# SCH_TRANSMITTER-WITH-ATMEGA328-VER-1_2_2.net
KiCad netlist of a schematic drawn in EasyEDA
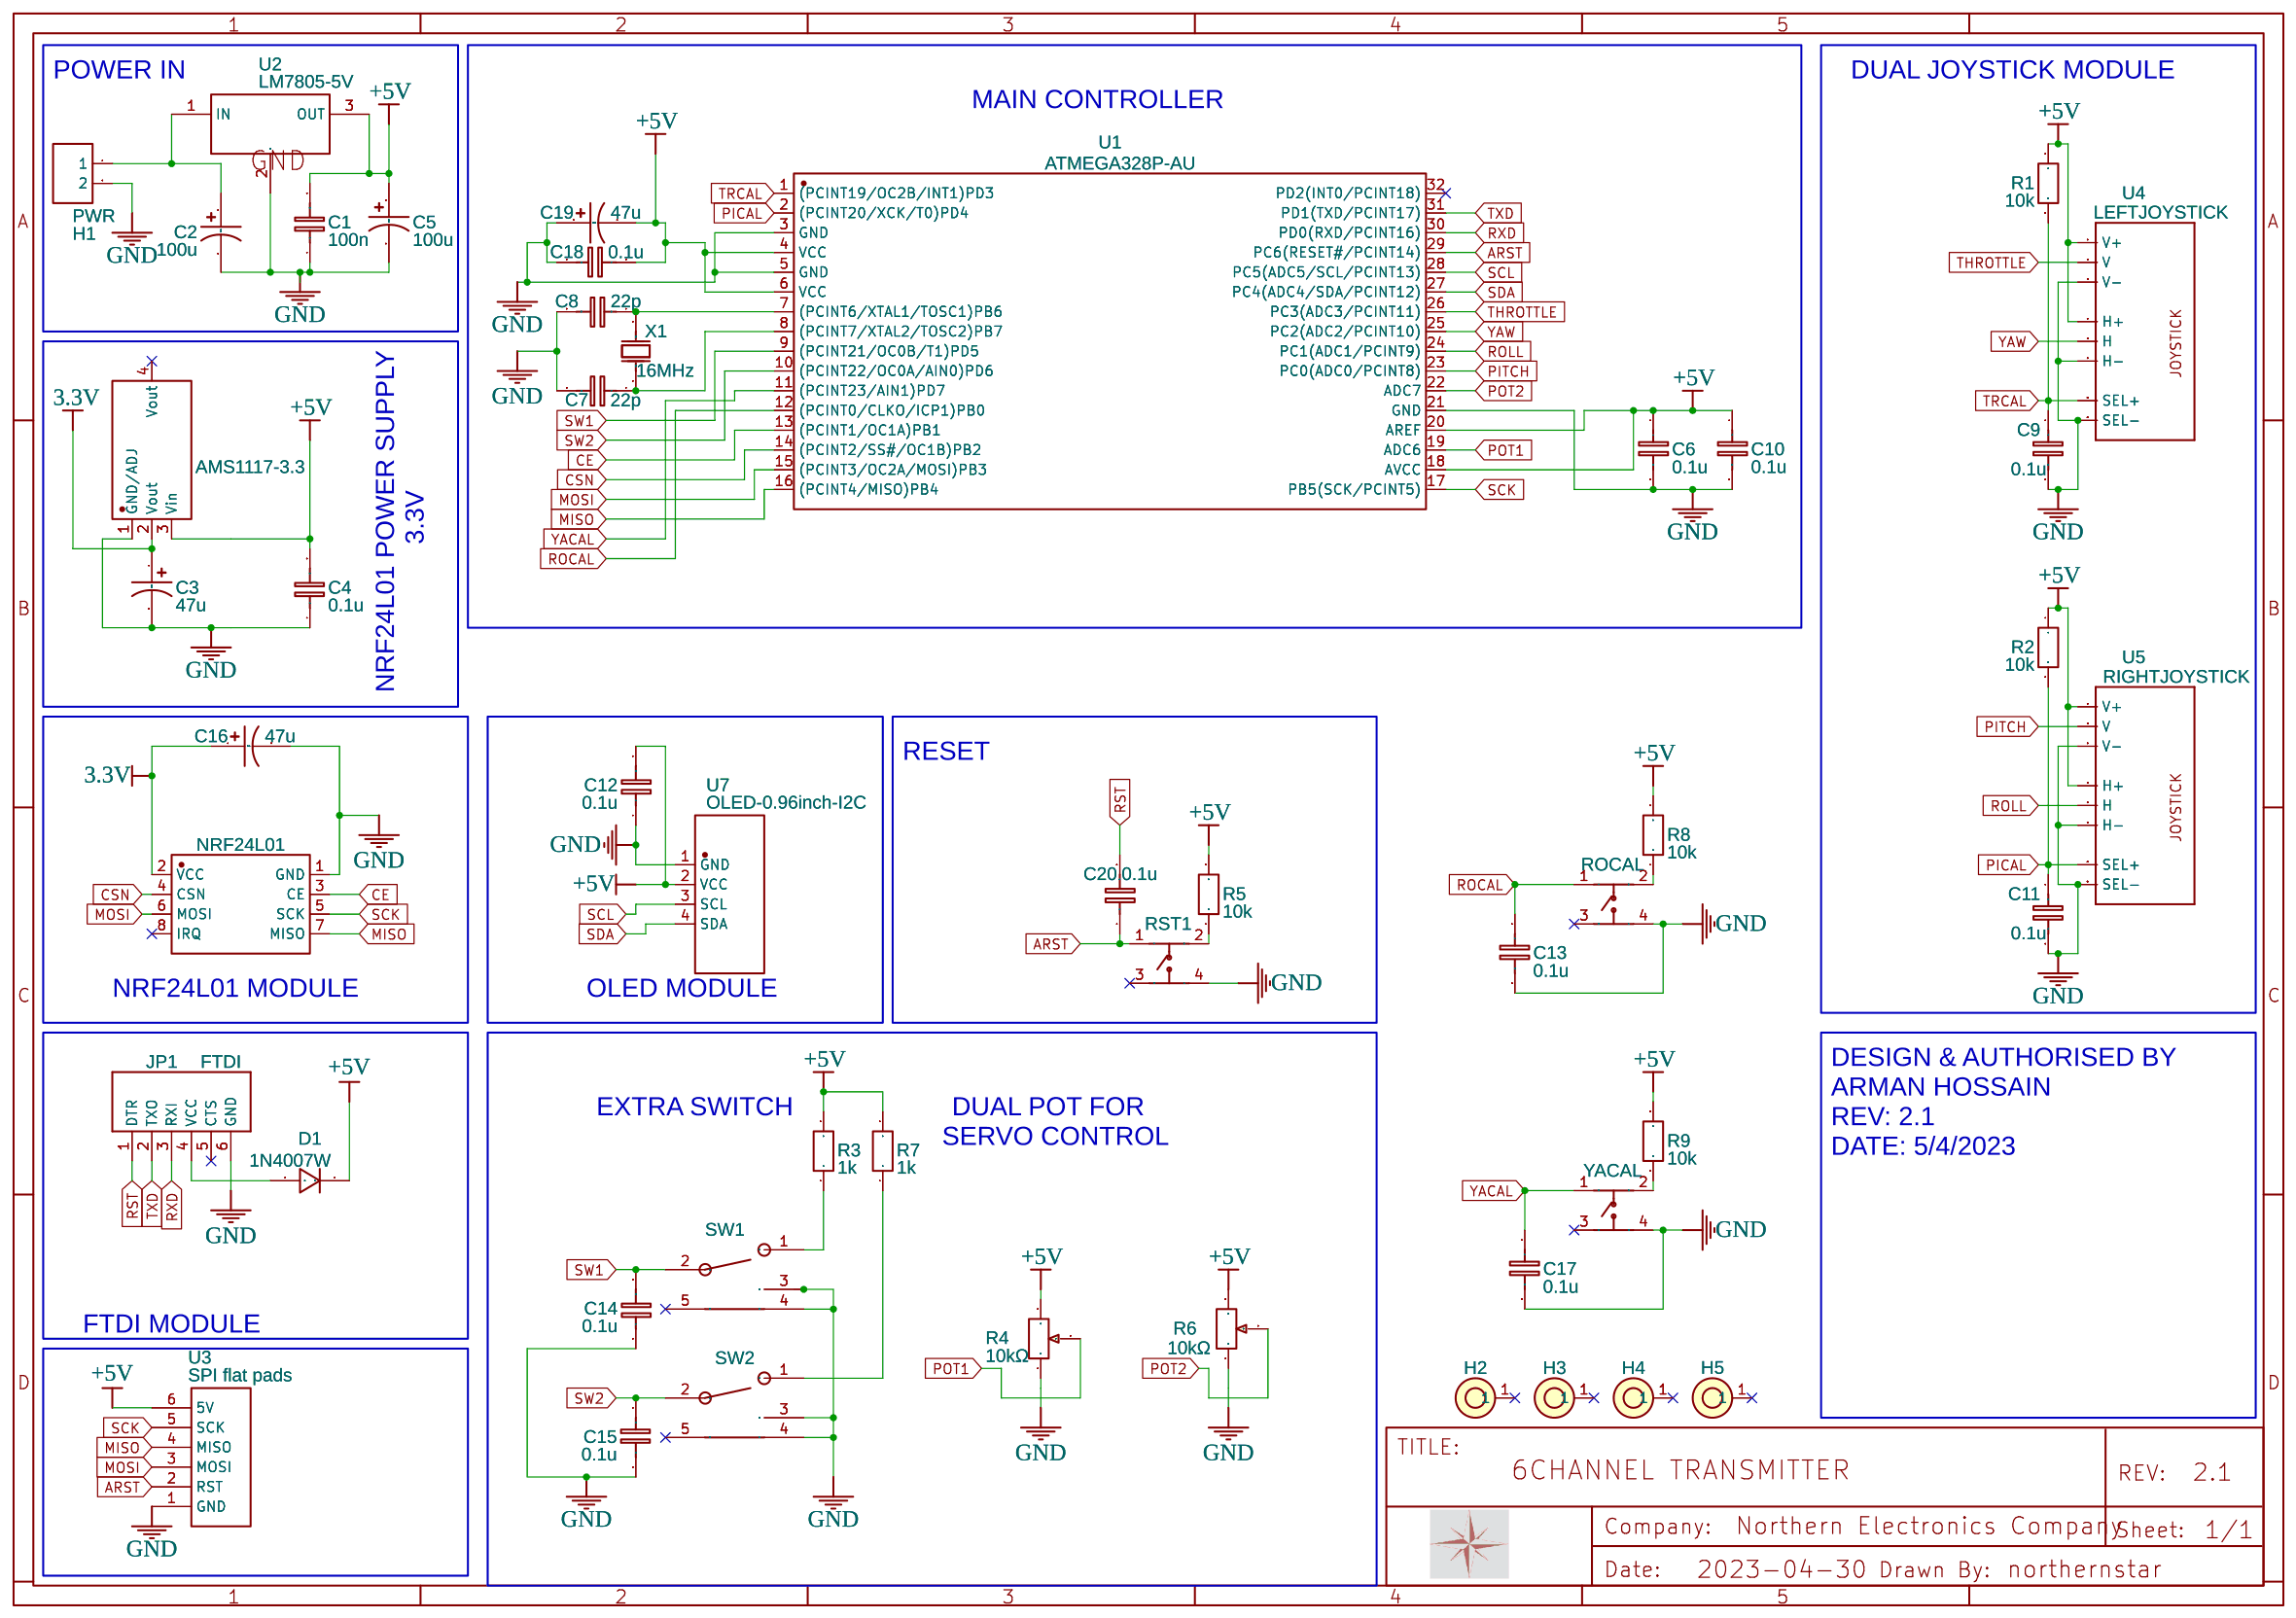
[diagram p0: schematic sheet]

(export (version "E")
  (design (tool "Eeschema 10.0.6"))
  (components
    (comp (ref "C1") (value "100n") (libsource (lib "") (part "C_RAD-0.2_EU_1")))
    (comp (ref "C2") (value "100u") (libsource (lib "") (part "CE_TH_D5.0×F2.0_US_2")))
    (comp (ref "C3") (value "47u") (libsource (lib "") (part "CE_TH_D5.0×F2.0_US_1")))
    (comp (ref "C4") (value "0.1u") (libsource (lib "") (part "C_1206_EU_3")))
    (comp (ref "C5") (value "100u") (libsource (lib "") (part "CE_TH_D5.0×F2.0_US_2")))
    (comp (ref "C6") (value "0.1u") (libsource (lib "") (part "C_1206_EU_5")))
    (comp (ref "C7") (value "22p") (libsource (lib "") (part "C_RAD-0.2_EU")))
    (comp (ref "C8") (value "22p") (libsource (lib "") (part "C_RAD-0.2_EU")))
    (comp (ref "C9") (value "0.1u") (libsource (lib "") (part "C_1206_EU_4")))
    (comp (ref "C10") (value "0.1u") (libsource (lib "") (part "C_1206_EU_5")))
    (comp (ref "C11") (value "0.1u") (libsource (lib "") (part "C_1206_EU_1")))
    (comp (ref "C12") (value "0.1u") (libsource (lib "") (part "C_1206_EU_6")))
    (comp (ref "C13") (value "0.1u") (libsource (lib "") (part "C_1206_EU_1")))
    (comp (ref "C14") (value "0.1u") (libsource (lib "") (part "C_1206_EU_6")))
    (comp (ref "C15") (value "0.1u") (libsource (lib "") (part "C_1206_EU_7")))
    (comp (ref "C16") (value "47u") (libsource (lib "") (part "CE_TH_D5.0×F2.0_US")))
    (comp (ref "C17") (value "0.1u") (libsource (lib "") (part "C_1206_EU_1")))
    (comp (ref "C18") (value "0.1u") (libsource (lib "") (part "C_1206_EU_2")))
    (comp (ref "C19") (value "47u") (libsource (lib "") (part "CE_TH_D5.0×F2.0_US_3")))
    (comp (ref "C20") (value "0.1u") (libsource (lib "") (part "C_1206_EU")))
    (comp (ref "D1")
      (value "1N4007W")
      (fields (field (name "Manufacturer") "BLUE ROCKET"))
      (libsource (lib "") (part "1N4007W"))
    )
    (comp (ref "H1") (value "PWR") (libsource (lib "") (part "HDR-F-2.54_1x2")))
    (comp (ref "H2") (value "M3 HOLE PLATED") (libsource (lib "") (part "M3 HOLE PLATED")))
    (comp (ref "H3") (value "M3 HOLE PLATED") (libsource (lib "") (part "M3 HOLE PLATED")))
    (comp (ref "H4") (value "M3 HOLE PLATED") (libsource (lib "") (part "M3 HOLE PLATED")))
    (comp (ref "H5") (value "M3 HOLE PLATED") (libsource (lib "") (part "M3 HOLE PLATED")))
    (comp (ref "JP1") (value "FTDI") (libsource (lib "") (part "FTDI")))
    (comp (ref "MK1")
      (value "NRF24L01")
      (fields (field (name "Manufacturer Part") "NF-04") (field (name "Manufacturer") "Ai-Thinker(安信可)"))
      (libsource (lib "") (part "NRF24L01"))
    )
    (comp (ref "NO1")
      (value "AMS1117-3.3")
      (fields (field (name "Manufacturer Part") "AMS1117-3.3-YJLTY"))
      (libsource (lib "") (part "AMS1117-3.3-YJLTY"))
    )
    (comp (ref "R1") (value "10k") (libsource (lib "") (part "R_1206_EU")))
    (comp (ref "R2") (value "10k") (libsource (lib "") (part "R_1206_EU")))
    (comp (ref "R3") (value "1k") (libsource (lib "") (part "R_1206_EU_1")))
    (comp (ref "R4")
      (value "10kΩ")
      (fields
        (field (name "Manufacturer Part") "RK16312A0BKH")
        (field (name "Manufacturer") "ALPSALPINE(阿尔卑斯阿尔派)")
      )
      (libsource (lib "") (part "A10K"))
    )
    (comp (ref "R5") (value "10k") (libsource (lib "") (part "R_1206_EU_1")))
    (comp (ref "R6")
      (value "10kΩ")
      (fields
        (field (name "Manufacturer Part") "RK16312A0BKH")
        (field (name "Manufacturer") "ALPSALPINE(阿尔卑斯阿尔派)")
      )
      (libsource (lib "") (part "A10K"))
    )
    (comp (ref "R7") (value "1k") (libsource (lib "") (part "R_1206_EU_1")))
    (comp (ref "R8") (value "10k") (libsource (lib "") (part "R_1206_EU_1")))
    (comp (ref "R9") (value "10k") (libsource (lib "") (part "R_1206_EU_1")))
    (comp (ref "ROCAL")
      (value "TSD001A08526A")
      (fields (field (name "Manufacturer") "BZCN(博众电气)"))
      (libsource (lib "") (part "TSD001A08526A_2"))
    )
    (comp (ref "RST1")
      (value "TSD001A08526A")
      (fields (field (name "Manufacturer") "BZCN(博众电气)"))
      (libsource (lib "") (part "TSD001A08526A"))
    )
    (comp (ref "SW1")
      (value "SW")
      (fields (field (name "Manufacturer Part") "100SP3T2B4M6RE") (field (name "Manufacturer") "E-Switch"))
      (libsource (lib "") (part "100SP3T2B4M6RE"))
    )
    (comp (ref "SW2")
      (value "100SP3T2B4M6RE")
      (fields (field (name "Manufacturer") "E-Switch"))
      (libsource (lib "") (part "100SP3T2B4M6RE"))
    )
    (comp (ref "U1") (value "ATMEGA328P-AU") (libsource (lib "") (part "ATMEGA328P-AU_C2851158")))
    (comp (ref "U2") (value "LM7805-5V") (libsource (lib "") (part "LM7805-5V")))
    (comp (ref "U3") (value "SPI flat pads") (libsource (lib "") (part "SPI flat pads")))
    (comp (ref "U4") (value "LEFTJOYSTICK") (libsource (lib "") (part "JOYSTICKPTH")))
    (comp (ref "U5") (value "RIGHTJOYSTICK") (libsource (lib "") (part "JOYSTICKPTH")))
    (comp (ref "U7")
      (value "OLED-0.96inch-I2C")
      (fields
        (field (name "Manufacturer Part") "ZJY096S0700BG01蓝色")
        (field (name "Manufacturer") "AZDelivery")
      )
      (libsource (lib "") (part "OLED-0.96inch-I2C"))
    )
    (comp (ref "X1")
      (value "16MHz")
      (fields (field (name "Manufacturer Part") "X49SD16MSD2SC") (field (name "Manufacturer") "YXC(扬兴晶振)"))
      (libsource (lib "") (part "X49SD16MSD2SC"))
    )
    (comp (ref "YACAL")
      (value "TSD001A08526A")
      (fields (field (name "Manufacturer") "BZCN(博众电气)"))
      (libsource (lib "") (part "TSD001A08526A_1"))
    )
  )
  (nets
    (net (code "1") (name "+5V") (class "Default")
      (node (ref "C1") (pin "2") (pinfunction "2_2") (pintype "unspecified"))
      (node (ref "C10") (pin "1") (pinfunction "1_1") (pintype "unspecified"))
      (node (ref "C12") (pin "2") (pinfunction "2_2") (pintype "unspecified"))
      (node (ref "C18") (pin "2") (pinfunction "2_2") (pintype "unspecified"))
      (node (ref "C19") (pin "2") (pinfunction "2_2") (pintype "unspecified"))
      (node (ref "C4") (pin "2") (pinfunction "2_2") (pintype "unspecified"))
      (node (ref "C5") (pin "1") (pinfunction "1_1") (pintype "unspecified"))
      (node (ref "C6") (pin "1") (pinfunction "1_1") (pintype "unspecified"))
      (node (ref "D1") (pin "1") (pinfunction "1_1") (pintype "unspecified"))
      (node (ref "NO1") (pin "3") (pinfunction "Vin_3") (pintype "unspecified"))
      (node (ref "R1") (pin "1") (pinfunction "1_1") (pintype "unspecified"))
      (node (ref "R2") (pin "1") (pinfunction "1_1") (pintype "unspecified"))
      (node (ref "R3") (pin "2") (pinfunction "2_2") (pintype "unspecified"))
      (node (ref "R4") (pin "3") (pinfunction "3_3") (pintype "input"))
      (node (ref "R5") (pin "2") (pinfunction "2_2") (pintype "unspecified"))
      (node (ref "R6") (pin "3") (pinfunction "3_3") (pintype "input"))
      (node (ref "R7") (pin "2") (pinfunction "2_2") (pintype "unspecified"))
      (node (ref "R8") (pin "2") (pinfunction "2_2") (pintype "unspecified"))
      (node (ref "R9") (pin "2") (pinfunction "2_2") (pintype "unspecified"))
      (node (ref "U1") (pin "18") (pinfunction "AVCC_18") (pintype "unspecified"))
      (node (ref "U1") (pin "20") (pinfunction "AREF_20") (pintype "unspecified"))
      (node (ref "U1") (pin "4") (pinfunction "VCC_4") (pintype "unspecified"))
      (node (ref "U1") (pin "6") (pinfunction "VCC_6") (pintype "unspecified"))
      (node (ref "U2") (pin "3") (pinfunction "OUT_3") (pintype "passive"))
      (node (ref "U3") (pin "6") (pinfunction "5V_6") (pintype "unspecified"))
      (node (ref "U4") (pin "H1") (pinfunction "H+_H1") (pintype "bidirectional"))
      (node (ref "U4") (pin "V1") (pinfunction "V+_V1") (pintype "bidirectional"))
      (node (ref "U5") (pin "H1") (pinfunction "H+_H1") (pintype "bidirectional"))
      (node (ref "U5") (pin "V1") (pinfunction "V+_V1") (pintype "bidirectional"))
      (node (ref "U7") (pin "2") (pinfunction "VCC_2") (pintype "unspecified"))
    )
    (net (code "2") (name "3.3V") (class "Default")
      (node (ref "C16") (pin "1") (pinfunction "1_1") (pintype "unspecified"))
      (node (ref "C3") (pin "1") (pinfunction "1_1") (pintype "unspecified"))
      (node (ref "MK1") (pin "2") (pinfunction "VCC_2") (pintype "unspecified"))
      (node (ref "NO1") (pin "2") (pinfunction "Vout_2") (pintype "unspecified"))
    )
    (net (code "3") (name "ARST") (class "Default")
      (node (ref "C20") (pin "1") (pinfunction "1_1") (pintype "unspecified"))
      (node (ref "RST1") (pin "1") (pinfunction "1_1") (pintype "unspecified"))
      (node (ref "U1") (pin "29") (pinfunction "PC6(RESET#/PCINT14)_29") (pintype "unspecified"))
      (node (ref "U3") (pin "2") (pinfunction "RST_2") (pintype "unspecified"))
    )
    (net (code "4") (name "CE") (class "Default")
      (node (ref "MK1") (pin "3") (pinfunction "CE_3") (pintype "unspecified"))
      (node (ref "U1") (pin "13") (pinfunction "(PCINT1/OC1A)PB1_13") (pintype "unspecified"))
    )
    (net (code "5") (name "CSN") (class "Default")
      (node (ref "MK1") (pin "4") (pinfunction "CSN_4") (pintype "unspecified"))
      (node (ref "U1") (pin "14") (pinfunction "(PCINT2/SS#/OC1B)PB2_14") (pintype "unspecified"))
    )
    (net (code "6") (name "GND") (class "Default")
      (node (ref "C1") (pin "1") (pinfunction "1_1") (pintype "unspecified"))
      (node (ref "C10") (pin "2") (pinfunction "2_2") (pintype "unspecified"))
      (node (ref "C11") (pin "2") (pinfunction "2_2") (pintype "unspecified"))
      (node (ref "C12") (pin "1") (pinfunction "1_1") (pintype "unspecified"))
      (node (ref "C13") (pin "2") (pinfunction "2_2") (pintype "unspecified"))
      (node (ref "C14") (pin "1") (pinfunction "1_1") (pintype "unspecified"))
      (node (ref "C15") (pin "2") (pinfunction "2_2") (pintype "unspecified"))
      (node (ref "C16") (pin "2") (pinfunction "2_2") (pintype "unspecified"))
      (node (ref "C17") (pin "2") (pinfunction "2_2") (pintype "unspecified"))
      (node (ref "C18") (pin "1") (pinfunction "1_1") (pintype "unspecified"))
      (node (ref "C19") (pin "1") (pinfunction "1_1") (pintype "unspecified"))
      (node (ref "C2") (pin "2") (pinfunction "2_2") (pintype "unspecified"))
      (node (ref "C3") (pin "2") (pinfunction "2_2") (pintype "unspecified"))
      (node (ref "C4") (pin "1") (pinfunction "1_1") (pintype "unspecified"))
      (node (ref "C5") (pin "2") (pinfunction "2_2") (pintype "unspecified"))
      (node (ref "C6") (pin "2") (pinfunction "2_2") (pintype "unspecified"))
      (node (ref "C7") (pin "2") (pinfunction "2_2") (pintype "unspecified"))
      (node (ref "C8") (pin "2") (pinfunction "2_2") (pintype "unspecified"))
      (node (ref "C9") (pin "2") (pinfunction "2_2") (pintype "unspecified"))
      (node (ref "H1") (pin "2") (pinfunction "2_2") (pintype "input"))
      (node (ref "JP1") (pin "6") (pinfunction "GND_6") (pintype "unspecified"))
      (node (ref "MK1") (pin "1") (pinfunction "GND_1") (pintype "unspecified"))
      (node (ref "NO1") (pin "1") (pinfunction "GND/ADJ_1") (pintype "unspecified"))
      (node (ref "R4") (pin "1") (pinfunction "1_1") (pintype "input"))
      (node (ref "R6") (pin "1") (pinfunction "1_1") (pintype "input"))
      (node (ref "ROCAL") (pin "4") (pinfunction "4_4") (pintype "unspecified"))
      (node (ref "RST1") (pin "4") (pinfunction "4_4") (pintype "unspecified"))
      (node (ref "SW1") (pin "3") (pinfunction "3_3") (pintype "input"))
      (node (ref "SW1") (pin "4") (pinfunction "4_4") (pintype "unspecified"))
      (node (ref "SW2") (pin "3") (pinfunction "3_3") (pintype "input"))
      (node (ref "SW2") (pin "4") (pinfunction "4_4") (pintype "unspecified"))
      (node (ref "U1") (pin "21") (pinfunction "GND_21") (pintype "unspecified"))
      (node (ref "U1") (pin "3") (pinfunction "GND_3") (pintype "unspecified"))
      (node (ref "U1") (pin "5") (pinfunction "GND_5") (pintype "unspecified"))
      (node (ref "U2") (pin "2") (pinfunction "GND_2") (pintype "passive"))
      (node (ref "U3") (pin "1") (pinfunction "GND_1") (pintype "unspecified"))
      (node (ref "U4") (pin "B2A") (pinfunction "SEL-_B2A") (pintype "bidirectional"))
      (node (ref "U4") (pin "H3") (pinfunction "H-_H3") (pintype "bidirectional"))
      (node (ref "U4") (pin "V3") (pinfunction "V-_V3") (pintype "bidirectional"))
      (node (ref "U5") (pin "B2A") (pinfunction "SEL-_B2A") (pintype "bidirectional"))
      (node (ref "U5") (pin "H3") (pinfunction "H-_H3") (pintype "bidirectional"))
      (node (ref "U5") (pin "V3") (pinfunction "V-_V3") (pintype "bidirectional"))
      (node (ref "U7") (pin "1") (pinfunction "GND_1") (pintype "unspecified"))
      (node (ref "YACAL") (pin "4") (pinfunction "4_4") (pintype "unspecified"))
    )
    (net (code "7") (name "MISO") (class "Default")
      (node (ref "MK1") (pin "7") (pinfunction "MISO_7") (pintype "unspecified"))
      (node (ref "U1") (pin "16") (pinfunction "(PCINT4/MISO)PB4_16") (pintype "unspecified"))
      (node (ref "U3") (pin "4") (pinfunction "MISO_4") (pintype "unspecified"))
    )
    (net (code "8") (name "MOSI") (class "Default")
      (node (ref "MK1") (pin "6") (pinfunction "MOSI_6") (pintype "unspecified"))
      (node (ref "U1") (pin "15") (pinfunction "(PCINT3/OC2A/MOSI)PB3_15") (pintype "unspecified"))
      (node (ref "U3") (pin "3") (pinfunction "MOSI_3") (pintype "unspecified"))
    )
    (net (code "9") (name "Net-(JP1-VCC)") (class "Default")
      (node (ref "D1") (pin "2") (pinfunction "2_2") (pintype "unspecified"))
      (node (ref "JP1") (pin "4") (pinfunction "VCC_4") (pintype "unspecified"))
    )
    (net (code "10") (name "Net-(R3-Pad1)") (class "Default")
      (node (ref "R3") (pin "1") (pinfunction "1_1") (pintype "unspecified"))
      (node (ref "SW1") (pin "1") (pinfunction "1_1") (pintype "input"))
    )
    (net (code "11") (name "Net-(R5-Pad1)") (class "Default")
      (node (ref "R5") (pin "1") (pinfunction "1_1") (pintype "unspecified"))
      (node (ref "RST1") (pin "2") (pinfunction "2_2") (pintype "unspecified"))
    )
    (net (code "12") (name "Net-(R7-Pad1)") (class "Default")
      (node (ref "R7") (pin "1") (pinfunction "1_1") (pintype "unspecified"))
      (node (ref "SW2") (pin "1") (pinfunction "1_1") (pintype "input"))
    )
    (net (code "13") (name "Net-(R8-Pad1)") (class "Default")
      (node (ref "R8") (pin "1") (pinfunction "1_1") (pintype "unspecified"))
      (node (ref "ROCAL") (pin "2") (pinfunction "2_2") (pintype "unspecified"))
    )
    (net (code "14") (name "Net-(R9-Pad1)") (class "Default")
      (node (ref "R9") (pin "1") (pinfunction "1_1") (pintype "unspecified"))
      (node (ref "YACAL") (pin "2") (pinfunction "2_2") (pintype "unspecified"))
    )
    (net (code "15") (name "Net-(U1-(PCINT6{slash}XTAL1{slash}TOSC1)PB6)") (class "Default")
      (node (ref "C8") (pin "1") (pinfunction "1_1") (pintype "unspecified"))
      (node (ref "U1") (pin "7") (pinfunction "(PCINT6/XTAL1/TOSC1)PB6_7") (pintype "unspecified"))
      (node (ref "X1") (pin "1") (pinfunction "OSC1_1") (pintype "input"))
    )
    (net (code "16") (name "Net-(U1-(PCINT7{slash}XTAL2{slash}TOSC2)PB7)") (class "Default")
      (node (ref "C7") (pin "1") (pinfunction "1_1") (pintype "unspecified"))
      (node (ref "U1") (pin "8") (pinfunction "(PCINT7/XTAL2/TOSC2)PB7_8") (pintype "unspecified"))
      (node (ref "X1") (pin "2") (pinfunction "OSC2_2") (pintype "input"))
    )
    (net (code "17") (name "Net-(U2-IN)") (class "Default")
      (node (ref "C2") (pin "1") (pinfunction "1_1") (pintype "unspecified"))
      (node (ref "H1") (pin "1") (pinfunction "1_1") (pintype "input"))
      (node (ref "U2") (pin "1") (pinfunction "IN_1") (pintype "passive"))
    )
    (net (code "18") (name "PICAL") (class "Default")
      (node (ref "C11") (pin "1") (pinfunction "1_1") (pintype "unspecified"))
      (node (ref "R2") (pin "2") (pinfunction "2_2") (pintype "unspecified"))
      (node (ref "U1") (pin "2") (pinfunction "(PCINT20/XCK/T0)PD4_2") (pintype "unspecified"))
      (node (ref "U5") (pin "B1A") (pinfunction "SEL+_B1A") (pintype "bidirectional"))
    )
    (net (code "19") (name "PITCH") (class "Default")
      (node (ref "U1") (pin "23") (pinfunction "PC0(ADC0/PCINT8)_23") (pintype "unspecified"))
      (node (ref "U5") (pin "V2") (pinfunction "V_V2") (pintype "bidirectional"))
    )
    (net (code "20") (name "POT1") (class "Default")
      (node (ref "R4") (pin "2") (pinfunction "2_2") (pintype "input"))
      (node (ref "U1") (pin "19") (pinfunction "ADC6_19") (pintype "unspecified"))
    )
    (net (code "21") (name "POT2") (class "Default")
      (node (ref "R6") (pin "2") (pinfunction "2_2") (pintype "input"))
      (node (ref "U1") (pin "22") (pinfunction "ADC7_22") (pintype "unspecified"))
    )
    (net (code "22") (name "ROCAL") (class "Default")
      (node (ref "C13") (pin "1") (pinfunction "1_1") (pintype "unspecified"))
      (node (ref "ROCAL") (pin "1") (pinfunction "1_1") (pintype "unspecified"))
      (node (ref "U1") (pin "12") (pinfunction "(PCINT0/CLKO/ICP1)PB0_12") (pintype "unspecified"))
    )
    (net (code "23") (name "ROLL") (class "Default")
      (node (ref "U1") (pin "24") (pinfunction "PC1(ADC1/PCINT9)_24") (pintype "unspecified"))
      (node (ref "U5") (pin "H2") (pinfunction "H_H2") (pintype "bidirectional"))
    )
    (net (code "24") (name "RST") (class "Default")
      (node (ref "C20") (pin "2") (pinfunction "2_2") (pintype "unspecified"))
      (node (ref "JP1") (pin "1") (pinfunction "DTR_1") (pintype "unspecified"))
    )
    (net (code "25") (name "RXD") (class "Default")
      (node (ref "JP1") (pin "3") (pinfunction "RXI_3") (pintype "unspecified"))
      (node (ref "U1") (pin "30") (pinfunction "PD0(RXD/PCINT16)_30") (pintype "unspecified"))
    )
    (net (code "26") (name "SCK") (class "Default")
      (node (ref "MK1") (pin "5") (pinfunction "SCK_5") (pintype "unspecified"))
      (node (ref "U1") (pin "17") (pinfunction "PB5(SCK/PCINT5)_17") (pintype "unspecified"))
      (node (ref "U3") (pin "5") (pinfunction "SCK_5") (pintype "unspecified"))
    )
    (net (code "27") (name "SCL") (class "Default")
      (node (ref "U1") (pin "28") (pinfunction "PC5(ADC5/SCL/PCINT13)_28") (pintype "unspecified"))
      (node (ref "U7") (pin "3") (pinfunction "SCL_3") (pintype "unspecified"))
    )
    (net (code "28") (name "SDA") (class "Default")
      (node (ref "U1") (pin "27") (pinfunction "PC4(ADC4/SDA/PCINT12)_27") (pintype "unspecified"))
      (node (ref "U7") (pin "4") (pinfunction "SDA_4") (pintype "unspecified"))
    )
    (net (code "29") (name "SW1") (class "Default")
      (node (ref "C14") (pin "2") (pinfunction "2_2") (pintype "unspecified"))
      (node (ref "SW1") (pin "2") (pinfunction "2_2") (pintype "input"))
      (node (ref "U1") (pin "9") (pinfunction "(PCINT21/OC0B/T1)PD5_9") (pintype "unspecified"))
    )
    (net (code "30") (name "SW2") (class "Default")
      (node (ref "C15") (pin "1") (pinfunction "1_1") (pintype "unspecified"))
      (node (ref "SW2") (pin "2") (pinfunction "2_2") (pintype "input"))
      (node (ref "U1") (pin "10") (pinfunction "(PCINT22/OC0A/AIN0)PD6_10") (pintype "unspecified"))
    )
    (net (code "31") (name "THROTTLE") (class "Default")
      (node (ref "U1") (pin "26") (pinfunction "PC3(ADC3/PCINT11)_26") (pintype "unspecified"))
      (node (ref "U4") (pin "V2") (pinfunction "V_V2") (pintype "bidirectional"))
    )
    (net (code "32") (name "TRCAL") (class "Default")
      (node (ref "C9") (pin "1") (pinfunction "1_1") (pintype "unspecified"))
      (node (ref "R1") (pin "2") (pinfunction "2_2") (pintype "unspecified"))
      (node (ref "U1") (pin "1") (pinfunction "(PCINT19/OC2B/INT1)PD3_1") (pintype "unspecified"))
      (node (ref "U4") (pin "B1A") (pinfunction "SEL+_B1A") (pintype "bidirectional"))
    )
    (net (code "33") (name "TXD") (class "Default")
      (node (ref "JP1") (pin "2") (pinfunction "TXO_2") (pintype "unspecified"))
      (node (ref "U1") (pin "31") (pinfunction "PD1(TXD/PCINT17)_31") (pintype "unspecified"))
    )
    (net (code "34") (name "YACAL") (class "Default")
      (node (ref "C17") (pin "1") (pinfunction "1_1") (pintype "unspecified"))
      (node (ref "U1") (pin "11") (pinfunction "(PCINT23/AIN1)PD7_11") (pintype "unspecified"))
      (node (ref "YACAL") (pin "1") (pinfunction "1_1") (pintype "unspecified"))
    )
    (net (code "35") (name "YAW") (class "Default")
      (node (ref "U1") (pin "25") (pinfunction "PC2(ADC2/PCINT10)_25") (pintype "unspecified"))
      (node (ref "U4") (pin "H2") (pinfunction "H_H2") (pintype "bidirectional"))
    )
    (net (code "36") (name "unconnected-(H2-Pad1)") (class "Default")
      (node (ref "H2") (pin "1") (pinfunction "1_1") (pintype "unspecified+no_connect"))
    )
    (net (code "37") (name "unconnected-(H3-Pad1)") (class "Default")
      (node (ref "H3") (pin "1") (pinfunction "1_1") (pintype "unspecified+no_connect"))
    )
    (net (code "38") (name "unconnected-(H4-Pad1)") (class "Default")
      (node (ref "H4") (pin "1") (pinfunction "1_1") (pintype "unspecified+no_connect"))
    )
    (net (code "39") (name "unconnected-(H5-Pad1)") (class "Default")
      (node (ref "H5") (pin "1") (pinfunction "1_1") (pintype "unspecified+no_connect"))
    )
    (net (code "40") (name "unconnected-(JP1-CTS-Pad5)") (class "Default")
      (node (ref "JP1") (pin "5") (pinfunction "CTS_5") (pintype "unspecified+no_connect"))
    )
    (net (code "41") (name "unconnected-(MK1-IRQ-Pad8)") (class "Default")
      (node (ref "MK1") (pin "8") (pinfunction "IRQ_8") (pintype "unspecified+no_connect"))
    )
    (net (code "42") (name "unconnected-(NO1-Vout-Pad4)") (class "Default")
      (node (ref "NO1") (pin "4") (pinfunction "Vout_4") (pintype "unspecified+no_connect"))
    )
    (net (code "43") (name "unconnected-(ROCAL-Pad3)") (class "Default")
      (node (ref "ROCAL") (pin "3") (pinfunction "3_3") (pintype "unspecified+no_connect"))
    )
    (net (code "44") (name "unconnected-(RST1-Pad3)") (class "Default")
      (node (ref "RST1") (pin "3") (pinfunction "3_3") (pintype "unspecified+no_connect"))
    )
    (net (code "45") (name "unconnected-(SW1-Pad5)") (class "Default")
      (node (ref "SW1") (pin "5") (pinfunction "5_5") (pintype "unspecified+no_connect"))
    )
    (net (code "46") (name "unconnected-(SW2-Pad5)") (class "Default")
      (node (ref "SW2") (pin "5") (pinfunction "5_5") (pintype "unspecified+no_connect"))
    )
    (net (code "47") (name "unconnected-(U1-PD2(INT0{slash}PCINT18)-Pad32)") (class "Default")
      (node (ref "U1") (pin "32") (pinfunction "PD2(INT0/PCINT18)_32") (pintype "unspecified+no_connect"))
    )
    (net (code "48") (name "unconnected-(YACAL-Pad3)") (class "Default")
      (node (ref "YACAL") (pin "3") (pinfunction "3_3") (pintype "unspecified+no_connect"))
    )
  )
)
